# Top_Level.net
KiCad netlist of a schematic drawn in Altium Designer
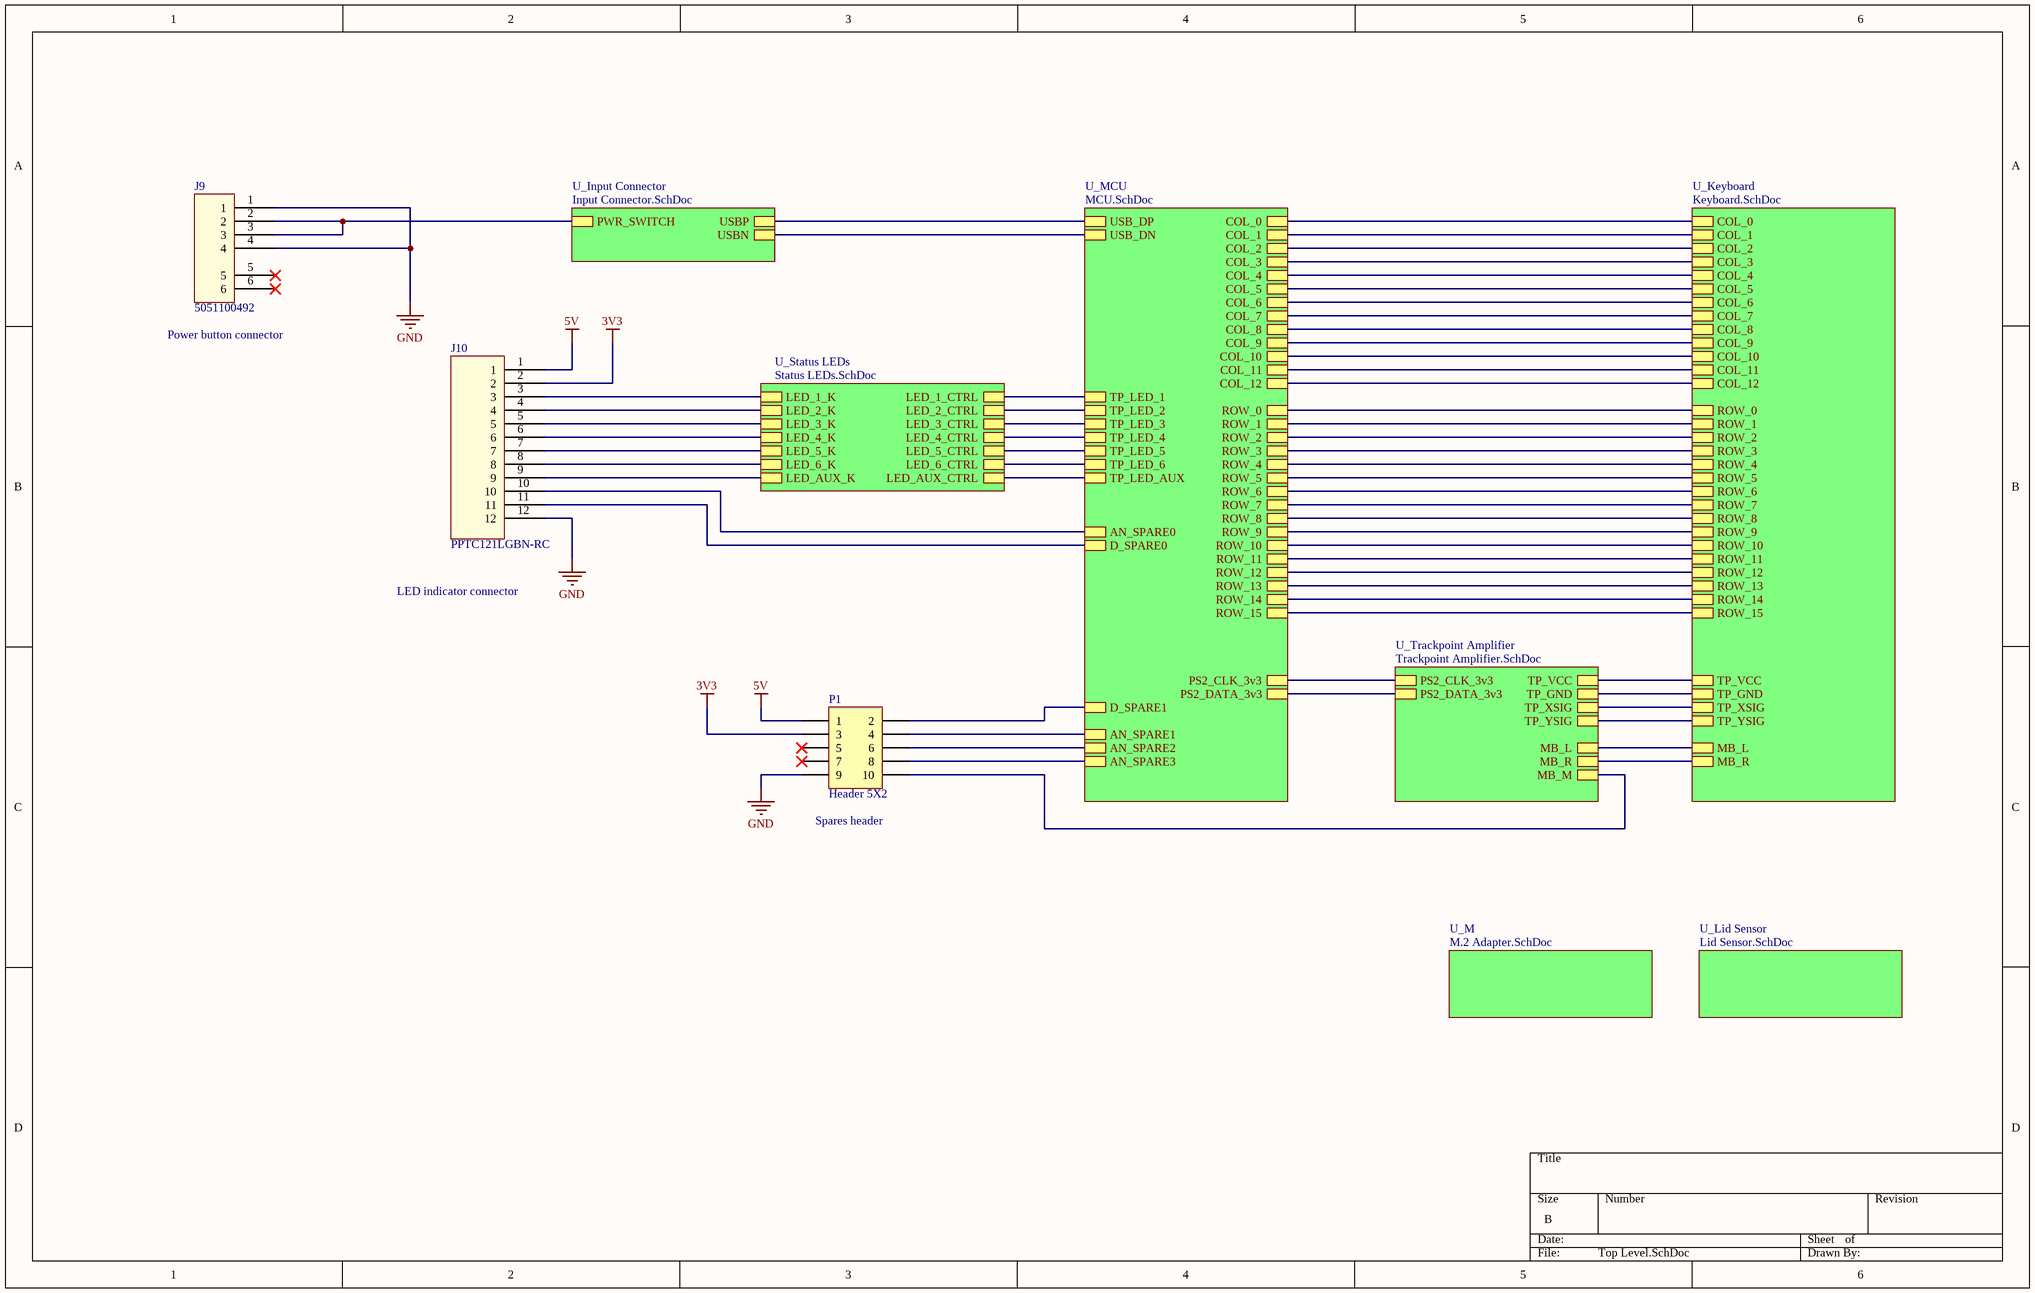
[diagram p0: Top Level.SchDoc]

(export (version "E")
  (design (tool "Eeschema 10.0.6"))
  (components
    (comp (ref "J9")
      (value "5051100492")
      (footprint "5051100492")
      (description "CONN FPC BOTTOM 4POS .5MM R/A")
      (libsource (lib "KBuchka-IntLib") (part "5051100492"))
    )
    (comp (ref "J10")
      (value "PPTC121LGBN-RC")
      (footprint "PPTC121LGBN-RC")
      (description "CONN HDR 12POS 0.1 TIN PCB R/A")
      (libsource (lib "KBuchka-IntLib") (part "PPTC121LGBN-RC"))
    )
    (comp (ref "P1")
      (value "Header 5X2")
      (footprint "HDR2X5")
      (description "Header, 5-Pin, Dual row")
      (fields (field (name "PUBLISHER") "Altium Limited"))
      (libsource (lib "Miscellaneous Connectors") (part "Header 5X2"))
    )
  )
  (nets
    (net (code "1") (name "/AN_SPARE0") (class "Default")
      (node (ref "J10") (pin "10") (pinfunction "10_10") (pintype "passive"))
    )
    (net (code "2") (name "/AN_SPARE1") (class "Default")
      (node (ref "P1") (pin "4") (pinfunction "4_4") (pintype "passive"))
    )
    (net (code "3") (name "/AN_SPARE2") (class "Default")
      (node (ref "P1") (pin "6") (pinfunction "6_6") (pintype "passive"))
    )
    (net (code "4") (name "/AN_SPARE3") (class "Default")
      (node (ref "P1") (pin "8") (pinfunction "8_8") (pintype "passive"))
    )
    (net (code "18") (name "/D_SPARE0") (class "Default")
      (node (ref "J10") (pin "11") (pinfunction "11_11") (pintype "passive"))
    )
    (net (code "19") (name "/D_SPARE1") (class "Default")
      (node (ref "P1") (pin "2") (pinfunction "2_2") (pintype "passive"))
    )
    (net (code "21") (name "/LED_1_K") (class "Default")
      (node (ref "J10") (pin "3") (pinfunction "3_3") (pintype "passive"))
    )
    (net (code "23") (name "/LED_2_K") (class "Default")
      (node (ref "J10") (pin "4") (pinfunction "4_4") (pintype "passive"))
    )
    (net (code "25") (name "/LED_3_K") (class "Default")
      (node (ref "J10") (pin "5") (pinfunction "5_5") (pintype "passive"))
    )
    (net (code "27") (name "/LED_4_K") (class "Default")
      (node (ref "J10") (pin "6") (pinfunction "6_6") (pintype "passive"))
    )
    (net (code "29") (name "/LED_5_K") (class "Default")
      (node (ref "J10") (pin "7") (pinfunction "7_7") (pintype "passive"))
    )
    (net (code "31") (name "/LED_6_K") (class "Default")
      (node (ref "J10") (pin "8") (pinfunction "8_8") (pintype "passive"))
    )
    (net (code "33") (name "/LED_AUX_K") (class "Default")
      (node (ref "J10") (pin "9") (pinfunction "9_9") (pintype "passive"))
    )
    (net (code "35") (name "/MB_M") (class "Default")
      (node (ref "P1") (pin "10") (pinfunction "10_10") (pintype "passive"))
    )
    (net (code "39") (name "/PWR_SWITCH") (class "Default")
      (node (ref "J9") (pin "2") (pinfunction "2_2") (pintype "passive"))
      (node (ref "J9") (pin "3") (pinfunction "3_3") (pintype "passive"))
    )
    (net (code "62") (name "3V3") (class "Default")
      (node (ref "J10") (pin "2") (pinfunction "2_2") (pintype "passive"))
      (node (ref "P1") (pin "3") (pinfunction "3_3") (pintype "passive"))
    )
    (net (code "63") (name "5V") (class "Default")
      (node (ref "J10") (pin "1") (pinfunction "1_1") (pintype "passive"))
      (node (ref "P1") (pin "1") (pinfunction "1_1") (pintype "passive"))
    )
    (net (code "64") (name "GND") (class "Default")
      (node (ref "J10") (pin "12") (pinfunction "12_12") (pintype "passive"))
      (node (ref "J9") (pin "1") (pinfunction "1_1") (pintype "passive"))
      (node (ref "J9") (pin "4") (pinfunction "4_4") (pintype "passive"))
      (node (ref "P1") (pin "9") (pinfunction "9_9") (pintype "passive"))
    )
    (net (code "65") (name "unconnected-(J9-Pad5)") (class "Default")
      (node (ref "J9") (pin "5") (pinfunction "5_5") (pintype "passive+no_connect"))
    )
    (net (code "66") (name "unconnected-(J9-Pad6)") (class "Default")
      (node (ref "J9") (pin "6") (pinfunction "6_6") (pintype "passive+no_connect"))
    )
    (net (code "67") (name "unconnected-(P1-Pad5)") (class "Default")
      (node (ref "P1") (pin "5") (pinfunction "5_5") (pintype "passive+no_connect"))
    )
    (net (code "68") (name "unconnected-(P1-Pad7)") (class "Default")
      (node (ref "P1") (pin "7") (pinfunction "7_7") (pintype "passive+no_connect"))
    )
  )
)
